# Relay_Conn.net
KiCad netlist of a schematic drawn in Altium Designer
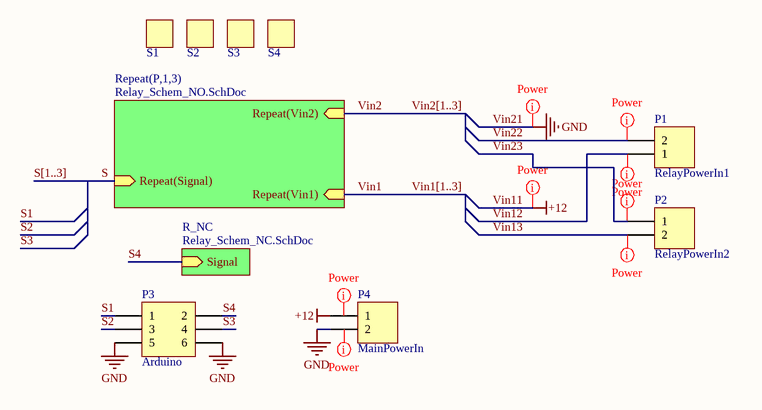
[diagram p0: Relay_Conn.SchDoc]

(export (version "E")
  (design (tool "Eeschema 10.0.6"))
  (components
    (comp (ref "P1")
      (value "RelayPowerIn1")
      (footprint "CONN-WAFER-2x1")
      (description "Header, 2-Pin")
      (fields (field (name "PUBLISHER") "Altium Limited"))
      (libsource (lib "") (part "Header 2_1"))
    )
    (comp (ref "P2")
      (value "RelayPowerIn2")
      (footprint "CONN-WAFER-2x1")
      (description "Header, 2-Pin")
      (fields (field (name "PUBLISHER") "Altium Limited"))
      (libsource (lib "Miscellaneous Connectors") (part "Header 2"))
    )
    (comp (ref "P3")
      (value "Arduino")
      (footprint "CONN-IDC-HARTING-2x3")
      (description "Header, 3-Pin, Dual row")
      (fields (field (name "PUBLISHER") "Altium Limited"))
      (libsource (lib "Miscellaneous Connectors") (part "Header 3X2"))
    )
    (comp (ref "P4")
      (value "MainPowerIn")
      (footprint "CONN-WAFER-2x1")
      (description "Header, 2-Pin")
      (fields (field (name "PUBLISHER") "Altium Limited"))
      (libsource (lib "Miscellaneous Connectors") (part "Header 2"))
    )
    (comp (ref "S1")
      (value "SCREW")
      (footprint "MECH-SCREW-M2.3")
      (description "Screw to add to schematics in order for them not to be removed from PCB")
      (libsource (lib "Tom_van_Rijn_Schlib") (part "SCREW"))
    )
    (comp (ref "S2")
      (value "SCREW")
      (footprint "MECH-SCREW-M2.3")
      (description "Screw to add to schematics in order for them not to be removed from PCB")
      (libsource (lib "Tom_van_Rijn_Schlib") (part "SCREW"))
    )
    (comp (ref "S3")
      (value "SCREW")
      (footprint "MECH-SCREW-M2.3")
      (description "Screw to add to schematics in order for them not to be removed from PCB")
      (libsource (lib "Tom_van_Rijn_Schlib") (part "SCREW"))
    )
    (comp (ref "S4")
      (value "SCREW")
      (footprint "MECH-SCREW-M2.3")
      (description "Screw to add to schematics in order for them not to be removed from PCB")
      (libsource (lib "Tom_van_Rijn_Schlib") (part "SCREW"))
    )
  )
  (nets
    (net (code "1") (name "+12") (class "Default")
      (node (ref "P4") (pin "1") (pinfunction "1_1") (pintype "passive"))
    )
    (net (code "3") (name "/S1") (class "Default")
      (node (ref "P3") (pin "1") (pinfunction "1_1") (pintype "passive"))
    )
    (net (code "4") (name "/S2") (class "Default")
      (node (ref "P3") (pin "3") (pinfunction "3_3") (pintype "passive"))
    )
    (net (code "5") (name "/S3") (class "Default")
      (node (ref "P3") (pin "4") (pinfunction "4_4") (pintype "passive"))
    )
    (net (code "6") (name "/S4") (class "Default")
      (node (ref "P3") (pin "2") (pinfunction "2_2") (pintype "passive"))
    )
    (net (code "12") (name "/Vin12") (class "Default")
      (node (ref "P1") (pin "1") (pinfunction "1_1") (pintype "passive"))
    )
    (net (code "13") (name "/Vin13") (class "Default")
      (node (ref "P2") (pin "2") (pinfunction "2_2") (pintype "passive"))
    )
    (net (code "14") (name "/Vin22") (class "Default")
      (node (ref "P1") (pin "2") (pinfunction "2_2") (pintype "passive"))
    )
    (net (code "15") (name "/Vin23") (class "Default")
      (node (ref "P2") (pin "1") (pinfunction "1_1") (pintype "passive"))
    )
    (net (code "16") (name "GND") (class "Default")
      (node (ref "P3") (pin "5") (pinfunction "5_5") (pintype "passive"))
      (node (ref "P3") (pin "6") (pinfunction "6_6") (pintype "passive"))
      (node (ref "P4") (pin "2") (pinfunction "2_2") (pintype "passive"))
    )
  )
)
